# carte_contr_le.net
KiCad netlist of a schematic drawn in EAGLE
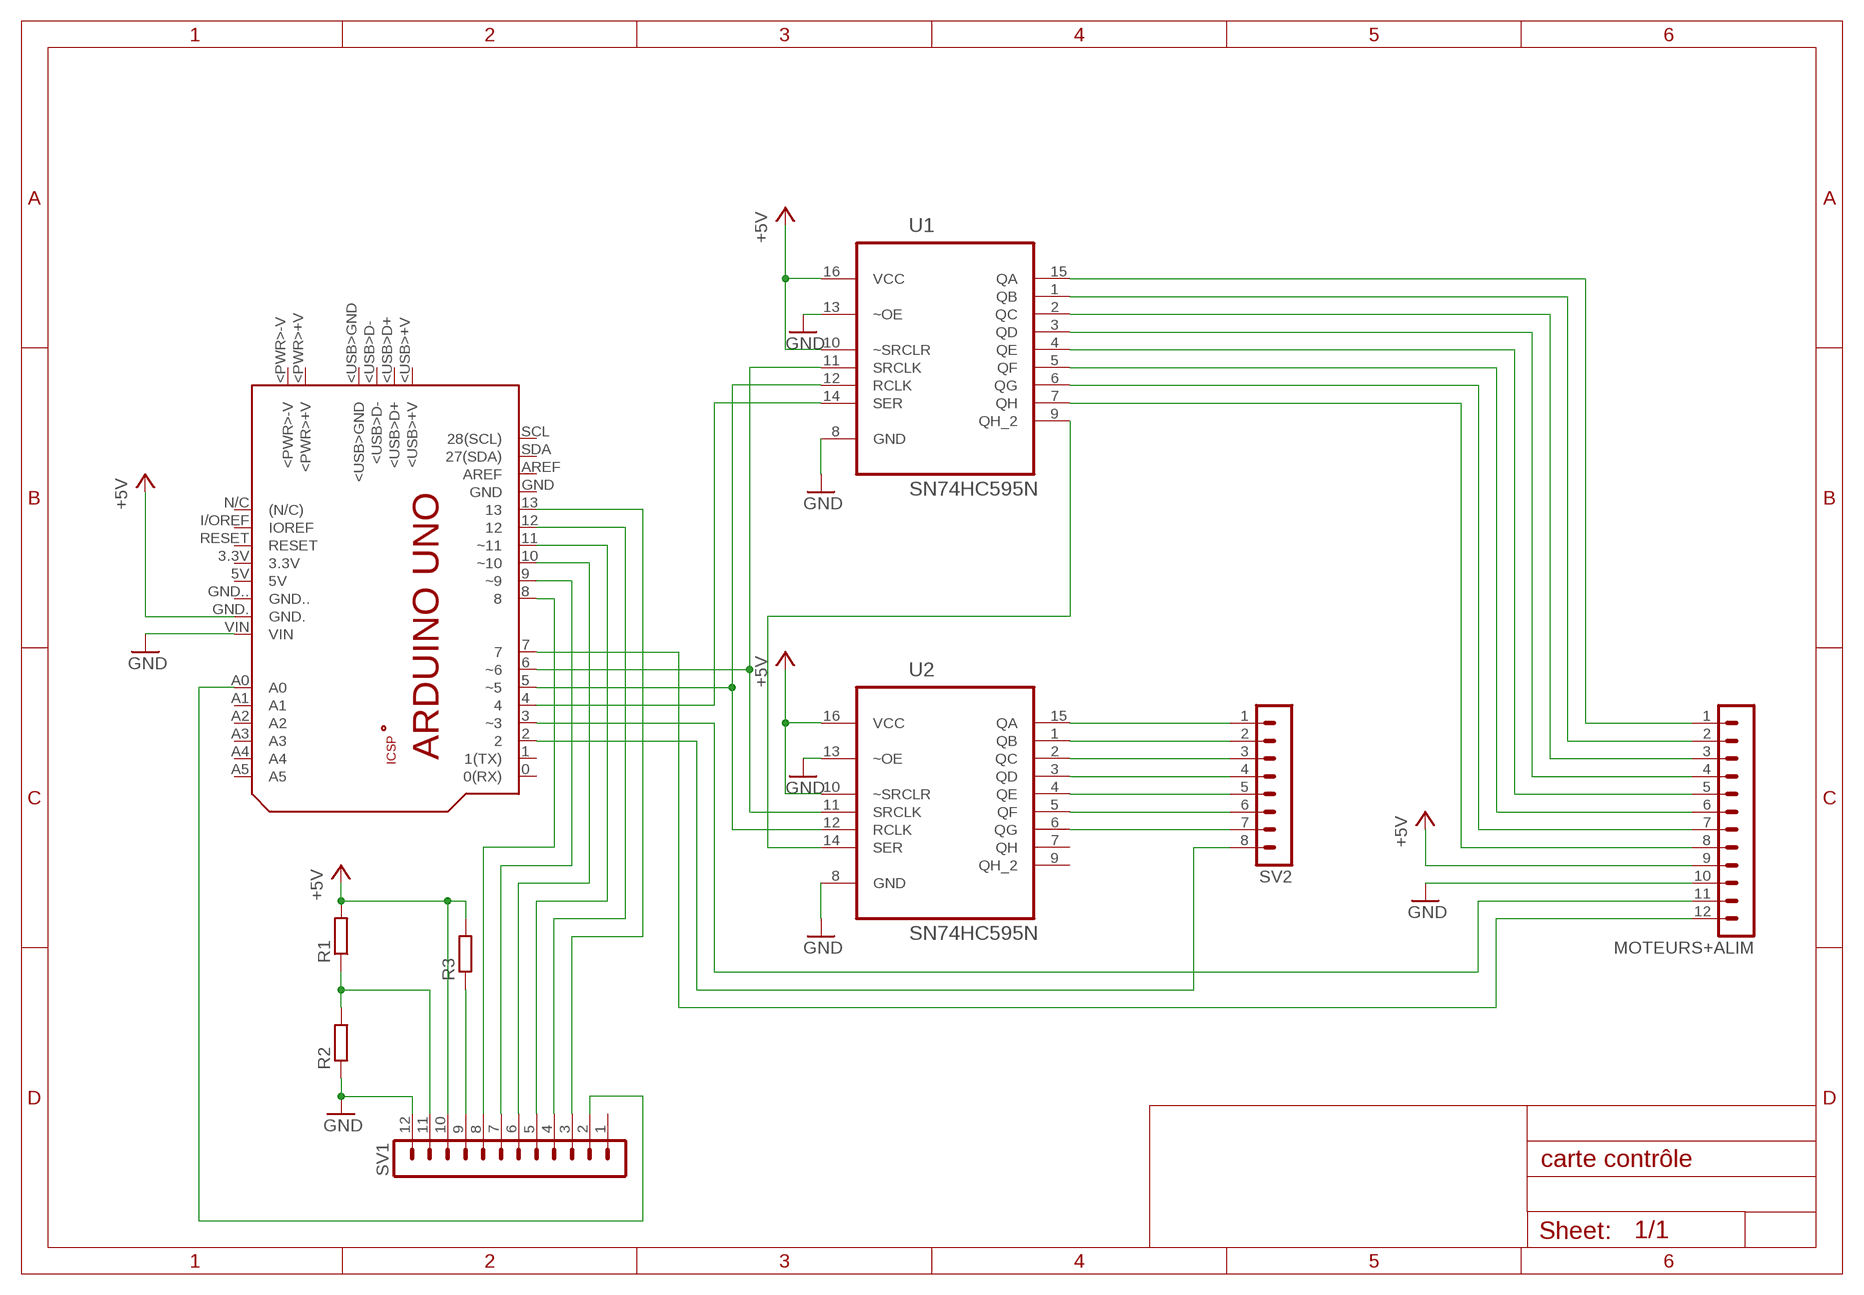
[diagram p0: schematic, sheet 1]

(export (version "E")
  (design (tool "Eeschema 10.0.6"))
  (components
    (comp (ref "MOTEURS+ALIM")
      (value "MA12-1")
      (footprint "eagle-import:MA12-1")
      (libsource (lib "eagle-import") (part "MA12-1"))
    )
    (comp (ref "PCB1")
      (value "ARDUINO_UNO")
      (footprint "eagle-import:ARDUINO_UNO")
      (libsource (lib "eagle-import") (part "ARDUINO_UNO"))
    )
    (comp (ref "R1")
      (value "R-EU_0207/10")
      (footprint "eagle-import:0207_10")
      (libsource (lib "eagle-import") (part "R-EU_0207/10"))
    )
    (comp (ref "R2")
      (value "R-EU_0207/10")
      (footprint "eagle-import:0207_10")
      (libsource (lib "eagle-import") (part "R-EU_0207/10"))
    )
    (comp (ref "R3")
      (value "R-EU_0207/10")
      (footprint "eagle-import:0207_10")
      (libsource (lib "eagle-import") (part "R-EU_0207/10"))
    )
    (comp (ref "SV1")
      (value "MA12-1")
      (footprint "eagle-import:MA12-1")
      (libsource (lib "eagle-import") (part "MA12-1"))
    )
    (comp (ref "SV2")
      (value "MA08-1")
      (footprint "eagle-import:MA08-1")
      (libsource (lib "eagle-import") (part "MA08-1"))
    )
    (comp (ref "U1")
      (value "SN74HC595N")
      (footprint "eagle-import:DIP254P762X508-16")
      (libsource (lib "eagle-import") (part "SN74HC595N"))
    )
    (comp (ref "U2")
      (value "SN74HC595N")
      (footprint "eagle-import:DIP254P762X508-16")
      (libsource (lib "eagle-import") (part "SN74HC595N"))
    )
  )
  (nets
    (net (code "1") (name "+5V") (class "Default")
      (node (ref "MOTEURS+ALIM") (pin "9") (pinfunction "9_9") (pintype "passive"))
      (node (ref "PCB1") (pin "GND.") (pinfunction "GND._GND.") (pintype "bidirectional"))
      (node (ref "R1") (pin "2") (pinfunction "2_2") (pintype "passive"))
      (node (ref "R3") (pin "2") (pinfunction "2_2") (pintype "passive"))
      (node (ref "SV1") (pin "10") (pinfunction "10_10") (pintype "passive"))
      (node (ref "U1") (pin "10") (pinfunction "~{SRCLR}_10") (pintype "input"))
      (node (ref "U1") (pin "16") (pinfunction "VCC_16") (pintype "power_in"))
      (node (ref "U2") (pin "10") (pinfunction "~{SRCLR}_10") (pintype "input"))
      (node (ref "U2") (pin "16") (pinfunction "VCC_16") (pintype "power_in"))
    )
    (net (code "2") (name "GND") (class "Default")
      (node (ref "MOTEURS+ALIM") (pin "10") (pinfunction "10_10") (pintype "passive"))
      (node (ref "PCB1") (pin "VIN") (pinfunction "VIN_VIN") (pintype "bidirectional"))
      (node (ref "R2") (pin "1") (pinfunction "1_1") (pintype "passive"))
      (node (ref "SV1") (pin "12") (pinfunction "12_12") (pintype "passive"))
      (node (ref "U1") (pin "13") (pinfunction "~{OE}_13") (pintype "input"))
      (node (ref "U1") (pin "8") (pinfunction "GND_8") (pintype "passive"))
      (node (ref "U2") (pin "13") (pinfunction "~{OE}_13") (pintype "input"))
      (node (ref "U2") (pin "8") (pinfunction "GND_8") (pintype "passive"))
    )
    (net (code "3") (name "Net-(MOTEURS+ALIM-Pad12)") (class "Default")
      (node (ref "MOTEURS+ALIM") (pin "12") (pinfunction "12_12") (pintype "passive"))
      (node (ref "PCB1") (pin "7") (pinfunction "7_7") (pintype "bidirectional"))
    )
    (net (code "4") (name "Net-(PCB1-Pad2)") (class "Default")
      (node (ref "PCB1") (pin "2") (pinfunction "2_2") (pintype "bidirectional"))
      (node (ref "SV2") (pin "8") (pinfunction "8_8") (pintype "passive"))
    )
    (net (code "5") (name "Net-(PCB1-Pad8)") (class "Default")
      (node (ref "PCB1") (pin "8") (pinfunction "8_8") (pintype "bidirectional"))
      (node (ref "SV1") (pin "8") (pinfunction "8_8") (pintype "passive"))
    )
    (net (code "6") (name "Net-(PCB1-Pad12)") (class "Default")
      (node (ref "PCB1") (pin "12") (pinfunction "12_12") (pintype "bidirectional"))
      (node (ref "SV1") (pin "4") (pinfunction "4_4") (pintype "passive"))
    )
    (net (code "7") (name "Net-(PCB1-Pad13)") (class "Default")
      (node (ref "PCB1") (pin "13") (pinfunction "13_13") (pintype "bidirectional"))
      (node (ref "SV1") (pin "3") (pinfunction "3_3") (pintype "passive"))
    )
    (net (code "8") (name "Net-(PCB1-PadA0)") (class "Default")
      (node (ref "PCB1") (pin "A0") (pinfunction "A0_A0") (pintype "bidirectional"))
      (node (ref "SV1") (pin "2") (pinfunction "2_2") (pintype "passive"))
    )
    (net (code "9") (name "Net-(PCB1-~{3})") (class "Default")
      (node (ref "MOTEURS+ALIM") (pin "11") (pinfunction "11_11") (pintype "passive"))
      (node (ref "PCB1") (pin "3") (pinfunction "~{3}_3") (pintype "bidirectional"))
    )
    (net (code "10") (name "Net-(PCB1-~{5})") (class "Default")
      (node (ref "PCB1") (pin "5") (pinfunction "~{5}_5") (pintype "bidirectional"))
      (node (ref "U1") (pin "12") (pinfunction "RCLK_12") (pintype "input"))
      (node (ref "U2") (pin "12") (pinfunction "RCLK_12") (pintype "input"))
    )
    (net (code "11") (name "Net-(PCB1-~{6})") (class "Default")
      (node (ref "PCB1") (pin "6") (pinfunction "~{6}_6") (pintype "bidirectional"))
      (node (ref "U1") (pin "11") (pinfunction "SRCLK_11") (pintype "input"))
      (node (ref "U2") (pin "11") (pinfunction "SRCLK_11") (pintype "input"))
    )
    (net (code "12") (name "Net-(PCB1-~{9})") (class "Default")
      (node (ref "PCB1") (pin "9") (pinfunction "~{9}_9") (pintype "bidirectional"))
      (node (ref "SV1") (pin "7") (pinfunction "7_7") (pintype "passive"))
    )
    (net (code "13") (name "Net-(PCB1-~{10})") (class "Default")
      (node (ref "PCB1") (pin "10") (pinfunction "~{10}_10") (pintype "bidirectional"))
      (node (ref "SV1") (pin "6") (pinfunction "6_6") (pintype "passive"))
    )
    (net (code "14") (name "Net-(PCB1-~{11})") (class "Default")
      (node (ref "PCB1") (pin "11") (pinfunction "~{11}_11") (pintype "bidirectional"))
      (node (ref "SV1") (pin "5") (pinfunction "5_5") (pintype "passive"))
    )
    (net (code "15") (name "Net-(R1-Pad1)") (class "Default")
      (node (ref "R1") (pin "1") (pinfunction "1_1") (pintype "passive"))
      (node (ref "R2") (pin "2") (pinfunction "2_2") (pintype "passive"))
      (node (ref "SV1") (pin "11") (pinfunction "11_11") (pintype "passive"))
    )
    (net (code "16") (name "Net-(R3-Pad1)") (class "Default")
      (node (ref "R3") (pin "1") (pinfunction "1_1") (pintype "passive"))
      (node (ref "SV1") (pin "9") (pinfunction "9_9") (pintype "passive"))
    )
    (net (code "17") (name "Net-(U1-QA)") (class "Default")
      (node (ref "MOTEURS+ALIM") (pin "1") (pinfunction "1_1") (pintype "passive"))
      (node (ref "U1") (pin "15") (pinfunction "QA_15") (pintype "output"))
    )
    (net (code "18") (name "Net-(U1-QB)") (class "Default")
      (node (ref "MOTEURS+ALIM") (pin "2") (pinfunction "2_2") (pintype "passive"))
      (node (ref "U1") (pin "1") (pinfunction "QB_1") (pintype "output"))
    )
    (net (code "19") (name "Net-(U1-QC)") (class "Default")
      (node (ref "MOTEURS+ALIM") (pin "3") (pinfunction "3_3") (pintype "passive"))
      (node (ref "U1") (pin "2") (pinfunction "QC_2") (pintype "output"))
    )
    (net (code "20") (name "Net-(U1-QD)") (class "Default")
      (node (ref "MOTEURS+ALIM") (pin "4") (pinfunction "4_4") (pintype "passive"))
      (node (ref "U1") (pin "3") (pinfunction "QD_3") (pintype "output"))
    )
    (net (code "21") (name "Net-(U1-QE)") (class "Default")
      (node (ref "MOTEURS+ALIM") (pin "5") (pinfunction "5_5") (pintype "passive"))
      (node (ref "U1") (pin "4") (pinfunction "QE_4") (pintype "output"))
    )
    (net (code "22") (name "Net-(U1-QF)") (class "Default")
      (node (ref "MOTEURS+ALIM") (pin "6") (pinfunction "6_6") (pintype "passive"))
      (node (ref "U1") (pin "5") (pinfunction "QF_5") (pintype "output"))
    )
    (net (code "23") (name "Net-(U1-QG)") (class "Default")
      (node (ref "MOTEURS+ALIM") (pin "7") (pinfunction "7_7") (pintype "passive"))
      (node (ref "U1") (pin "6") (pinfunction "QG_6") (pintype "output"))
    )
    (net (code "24") (name "Net-(U1-QH)") (class "Default")
      (node (ref "MOTEURS+ALIM") (pin "8") (pinfunction "8_8") (pintype "passive"))
      (node (ref "U1") (pin "7") (pinfunction "QH_7") (pintype "output"))
    )
    (net (code "25") (name "Net-(U1-QH_2)") (class "Default")
      (node (ref "U1") (pin "9") (pinfunction "QH_2_9") (pintype "output"))
      (node (ref "U2") (pin "14") (pinfunction "SER_14") (pintype "input"))
    )
    (net (code "26") (name "Net-(U1-SER)") (class "Default")
      (node (ref "PCB1") (pin "4") (pinfunction "4_4") (pintype "bidirectional"))
      (node (ref "U1") (pin "14") (pinfunction "SER_14") (pintype "input"))
    )
    (net (code "27") (name "Net-(U2-QA)") (class "Default")
      (node (ref "SV2") (pin "1") (pinfunction "1_1") (pintype "passive"))
      (node (ref "U2") (pin "15") (pinfunction "QA_15") (pintype "output"))
    )
    (net (code "28") (name "Net-(U2-QB)") (class "Default")
      (node (ref "SV2") (pin "2") (pinfunction "2_2") (pintype "passive"))
      (node (ref "U2") (pin "1") (pinfunction "QB_1") (pintype "output"))
    )
    (net (code "29") (name "Net-(U2-QC)") (class "Default")
      (node (ref "SV2") (pin "3") (pinfunction "3_3") (pintype "passive"))
      (node (ref "U2") (pin "2") (pinfunction "QC_2") (pintype "output"))
    )
    (net (code "30") (name "Net-(U2-QD)") (class "Default")
      (node (ref "SV2") (pin "4") (pinfunction "4_4") (pintype "passive"))
      (node (ref "U2") (pin "3") (pinfunction "QD_3") (pintype "output"))
    )
    (net (code "31") (name "Net-(U2-QE)") (class "Default")
      (node (ref "SV2") (pin "5") (pinfunction "5_5") (pintype "passive"))
      (node (ref "U2") (pin "4") (pinfunction "QE_4") (pintype "output"))
    )
    (net (code "32") (name "Net-(U2-QF)") (class "Default")
      (node (ref "SV2") (pin "6") (pinfunction "6_6") (pintype "passive"))
      (node (ref "U2") (pin "5") (pinfunction "QF_5") (pintype "output"))
    )
    (net (code "33") (name "Net-(U2-QG)") (class "Default")
      (node (ref "SV2") (pin "7") (pinfunction "7_7") (pintype "passive"))
      (node (ref "U2") (pin "6") (pinfunction "QG_6") (pintype "output"))
    )
    (net (code "34") (name "unconnected-(PCB1-(N{slash}C)-PadN{slash}C)") (class "Default")
      (node (ref "PCB1") (pin "N/C") (pinfunction "(N/C)_N/C") (pintype "bidirectional"))
    )
    (net (code "35") (name "unconnected-(PCB1-0(RX)-Pad0)") (class "Default")
      (node (ref "PCB1") (pin "0") (pinfunction "0(RX)_0") (pintype "bidirectional"))
    )
    (net (code "36") (name "unconnected-(PCB1-1(TX)-Pad1)") (class "Default")
      (node (ref "PCB1") (pin "1") (pinfunction "1(TX)_1") (pintype "bidirectional"))
    )
    (net (code "37") (name "unconnected-(PCB1-27(SDA)-PadSDA)") (class "Default")
      (node (ref "PCB1") (pin "SDA") (pinfunction "27(SDA)_SDA") (pintype "bidirectional"))
    )
    (net (code "38") (name "unconnected-(PCB1-28(SCL)-PadSCL)") (class "Default")
      (node (ref "PCB1") (pin "SCL") (pinfunction "28(SCL)_SCL") (pintype "bidirectional"))
    )
    (net (code "39") (name "unconnected-(PCB1-IOREF-PadI{slash}OREF)") (class "Default")
      (node (ref "PCB1") (pin "I/OREF") (pinfunction "IOREF_I/OREF") (pintype "bidirectional"))
    )
    (net (code "40") (name "unconnected-(PCB1-Pad+5V)") (class "Default")
      (node (ref "PCB1") (pin "+5V") (pinfunction "+5V_+5V") (pintype "bidirectional"))
    )
    (net (code "41") (name "unconnected-(PCB1-Pad3.3V)") (class "Default")
      (node (ref "PCB1") (pin "3.3V") (pinfunction "3.3V_3.3V") (pintype "bidirectional"))
    )
    (net (code "42") (name "unconnected-(PCB1-Pad5V)") (class "Default")
      (node (ref "PCB1") (pin "5V") (pinfunction "5V_5V") (pintype "bidirectional"))
    )
    (net (code "43") (name "unconnected-(PCB1-Pad<PWR>+V)") (class "Default")
      (node (ref "PCB1") (pin "<PWR>+V") (pinfunction "<PWR>+V_<PWR>+V") (pintype "bidirectional"))
    )
    (net (code "44") (name "unconnected-(PCB1-Pad<PWR>-V)") (class "Default")
      (node (ref "PCB1") (pin "<PWR>-V") (pinfunction "<PWR>-V_<PWR>-V") (pintype "bidirectional"))
    )
    (net (code "45") (name "unconnected-(PCB1-Pad<USB>+V)") (class "Default")
      (node (ref "PCB1") (pin "<USB>+V") (pinfunction "<USB>+V_<USB>+V") (pintype "bidirectional"))
    )
    (net (code "46") (name "unconnected-(PCB1-Pad<USB>D+)") (class "Default")
      (node (ref "PCB1") (pin "<USB>D+") (pinfunction "<USB>D+_<USB>D+") (pintype "bidirectional"))
    )
    (net (code "47") (name "unconnected-(PCB1-Pad<USB>D-)") (class "Default")
      (node (ref "PCB1") (pin "<USB>D-") (pinfunction "<USB>D-_<USB>D-") (pintype "bidirectional"))
    )
    (net (code "48") (name "unconnected-(PCB1-Pad<USB>GND)") (class "Default")
      (node (ref "PCB1") (pin "<USB>GND") (pinfunction "<USB>GND_<USB>GND") (pintype "bidirectional"))
    )
    (net (code "49") (name "unconnected-(PCB1-PadA1)") (class "Default")
      (node (ref "PCB1") (pin "A1") (pinfunction "A1_A1") (pintype "bidirectional"))
    )
    (net (code "50") (name "unconnected-(PCB1-PadA2)") (class "Default")
      (node (ref "PCB1") (pin "A2") (pinfunction "A2_A2") (pintype "bidirectional"))
    )
    (net (code "51") (name "unconnected-(PCB1-PadA3)") (class "Default")
      (node (ref "PCB1") (pin "A3") (pinfunction "A3_A3") (pintype "bidirectional"))
    )
    (net (code "52") (name "unconnected-(PCB1-PadA4)") (class "Default")
      (node (ref "PCB1") (pin "A4") (pinfunction "A4_A4") (pintype "bidirectional"))
    )
    (net (code "53") (name "unconnected-(PCB1-PadA5)") (class "Default")
      (node (ref "PCB1") (pin "A5") (pinfunction "A5_A5") (pintype "bidirectional"))
    )
    (net (code "54") (name "unconnected-(PCB1-PadAREF)") (class "Default")
      (node (ref "PCB1") (pin "AREF") (pinfunction "AREF_AREF") (pintype "bidirectional"))
    )
    (net (code "55") (name "unconnected-(PCB1-PadGND)") (class "Default")
      (node (ref "PCB1") (pin "GND") (pinfunction "GND_GND") (pintype "bidirectional"))
    )
    (net (code "56") (name "unconnected-(PCB1-PadGND..)") (class "Default")
      (node (ref "PCB1") (pin "GND..") (pinfunction "GND.._GND..") (pintype "bidirectional"))
    )
    (net (code "57") (name "unconnected-(PCB1-PadGND_)") (class "Default")
      (node (ref "PCB1") (pin "GND_") (pinfunction "GND__GND_") (pintype "bidirectional"))
    )
    (net (code "58") (name "unconnected-(PCB1-PadMISO)") (class "Default")
      (node (ref "PCB1") (pin "MISO") (pinfunction "MISO_MISO") (pintype "bidirectional"))
    )
    (net (code "59") (name "unconnected-(PCB1-PadMOSI)") (class "Default")
      (node (ref "PCB1") (pin "MOSI") (pinfunction "MOSI_MOSI") (pintype "bidirectional"))
    )
    (net (code "60") (name "unconnected-(PCB1-PadRESET)") (class "Default")
      (node (ref "PCB1") (pin "RESET") (pinfunction "RESET_RESET") (pintype "bidirectional"))
    )
    (net (code "61") (name "unconnected-(PCB1-PadRESET.)") (class "Default")
      (node (ref "PCB1") (pin "RESET.") (pinfunction "RESET._RESET.") (pintype "bidirectional"))
    )
    (net (code "62") (name "unconnected-(PCB1-PadSCK)") (class "Default")
      (node (ref "PCB1") (pin "SCK") (pinfunction "SCK_SCK") (pintype "bidirectional"))
    )
    (net (code "63") (name "unconnected-(SV1-Pad1)") (class "Default")
      (node (ref "SV1") (pin "1") (pinfunction "1_1") (pintype "passive"))
    )
    (net (code "64") (name "unconnected-(U2-QH-Pad7)") (class "Default")
      (node (ref "U2") (pin "7") (pinfunction "QH_7") (pintype "output"))
    )
    (net (code "65") (name "unconnected-(U2-QH_2-Pad9)") (class "Default")
      (node (ref "U2") (pin "9") (pinfunction "QH_2_9") (pintype "output"))
    )
  )
)
